# 800U-R3N3_V1_0.net
KiCad netlist of a schematic drawn in Altium Designer
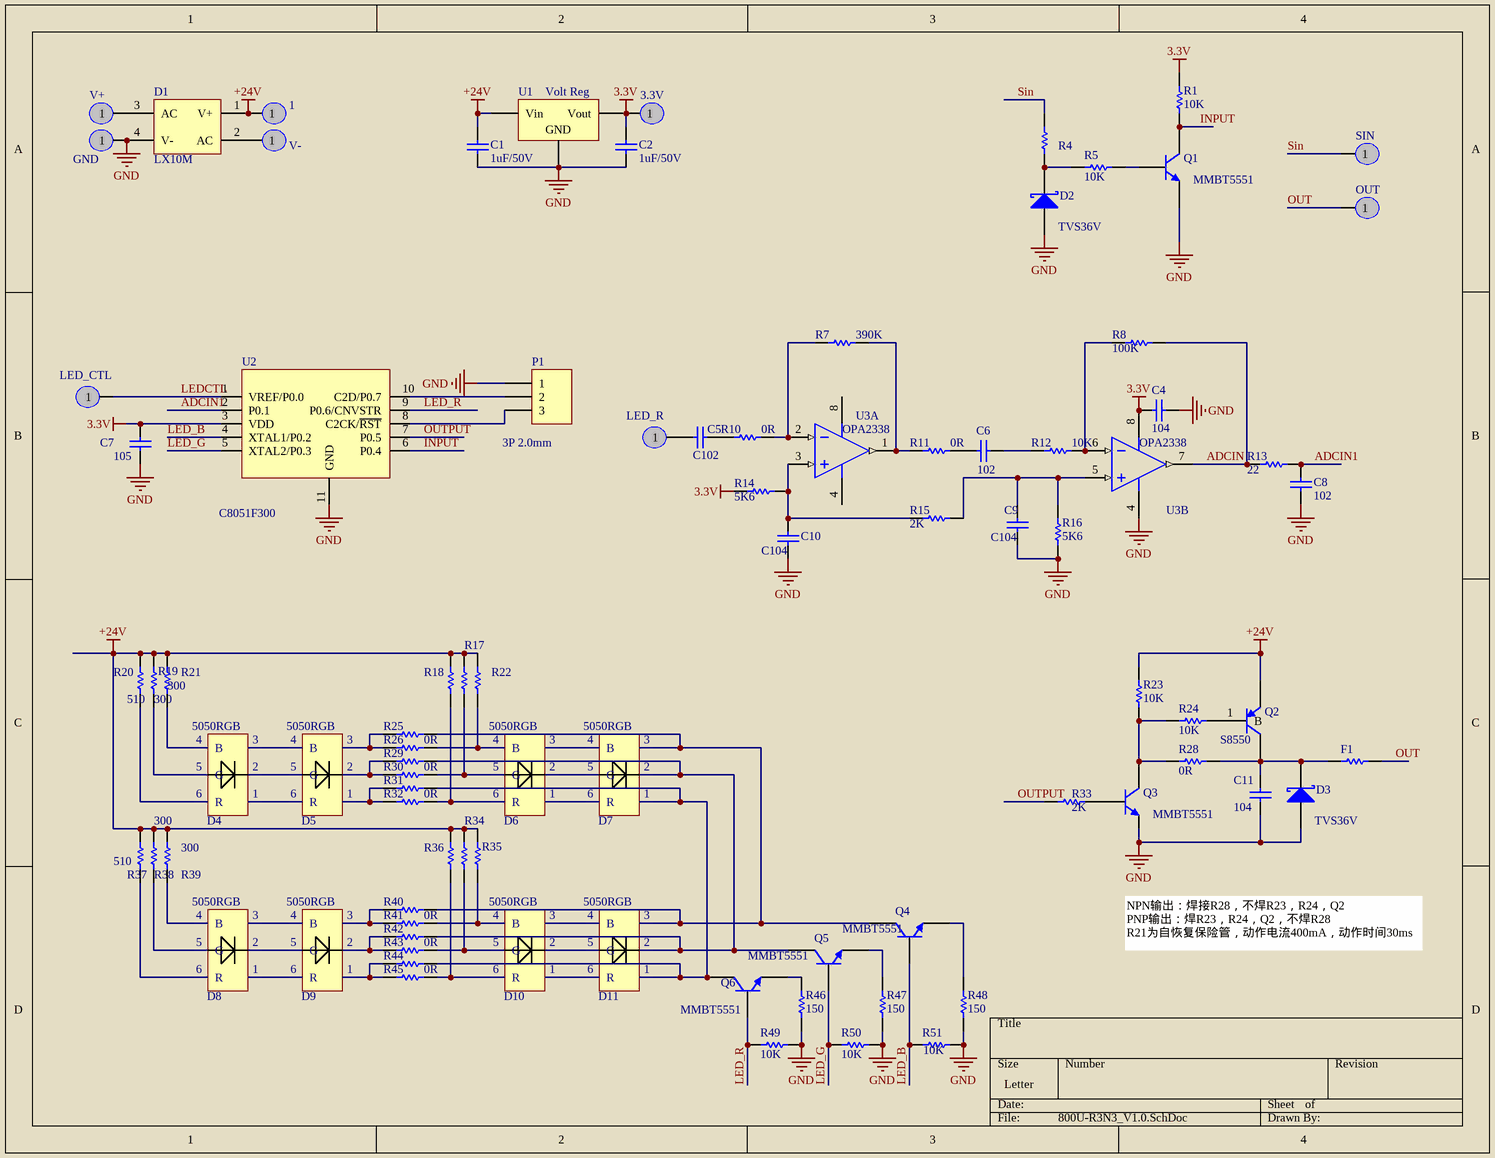
[diagram p0: 800U-R3N3_V1.0.SchDoc]

(export (version "E")
  (design (tool "Eeschema 10.0.6"))
  (components
    (comp (ref "1") (value "~") (footprint "HOLE_SMD") (libsource (lib "MODBUS_V1.0") (part "焊盘")))
    (comp (ref "3.3V") (value "~") (footprint "HOLE_SMD") (libsource (lib "MODBUS_V1.0") (part "焊盘")))
    (comp (ref "C1")
      (value "1uF/50V")
      (footprint "C0603")
      (description "贴片电容")
      (fields (field (name "PUBLISHER") "Altium Limited"))
      (libsource (lib "Miscellaneous Devices") (part "Cap"))
    )
    (comp (ref "C2")
      (value "1uF/50V")
      (footprint "C0603")
      (description "贴片电容")
      (fields (field (name "PUBLISHER") "Altium Limited"))
      (libsource (lib "Miscellaneous Devices") (part "Cap"))
    )
    (comp (ref "C4")
      (value "104")
      (footprint "C0603")
      (description "Capacitor")
      (fields (field (name "Comment") "C106") (field (name "PUBLISHER") "Altium Limited"))
      (libsource (lib "TMJD1.0") (part "Cap"))
    )
    (comp (ref "C5")
      (value "C102")
      (footprint "C0603")
      (description "Capacitor")
      (fields (field (name "Comment") "C104") (field (name "PUBLISHER") "Altium Limited"))
      (libsource (lib "TMJD1.0") (part "Cap"))
    )
    (comp (ref "C6")
      (value "102")
      (footprint "C0603")
      (description "Capacitor")
      (fields (field (name "Comment") "C104") (field (name "PUBLISHER") "Altium Limited"))
      (libsource (lib "TMJD1.0") (part "Cap"))
    )
    (comp (ref "C7")
      (value "105")
      (footprint "C0603")
      (description "贴片电容")
      (fields (field (name "PUBLISHER") "Altium Limited"))
      (libsource (lib "TMJD1.0") (part "Cap"))
    )
    (comp (ref "C8")
      (value "102")
      (footprint "C0603")
      (description "Capacitor")
      (fields (field (name "Comment") "C104") (field (name "PUBLISHER") "Altium Limited"))
      (libsource (lib "TMJD1.0") (part "Cap"))
    )
    (comp (ref "C9")
      (value "C104")
      (footprint "C0603")
      (description "Capacitor")
      (fields (field (name "PUBLISHER") "Altium Limited"))
      (libsource (lib "TMJD1.0") (part "Cap"))
    )
    (comp (ref "C10")
      (value "C104")
      (footprint "C0603")
      (description "Capacitor")
      (fields (field (name "PUBLISHER") "Altium Limited"))
      (libsource (lib "TMJD1.0") (part "Cap"))
    )
    (comp (ref "C11")
      (value "104")
      (footprint "C0603")
      (description "贴片电容")
      (fields (field (name "PUBLISHER") "Altium Limited"))
      (libsource (lib "TMJD1.0") (part "Cap"))
    )
    (comp (ref "D1")
      (value "LX10M")
      (footprint "桥堆 3.8*3.5")
      (description "贴片桥堆")
      (libsource (lib "Miscellaneous Devices") (part "Bridge2"))
    )
    (comp (ref "D2")
      (value "TVS36V")
      (footprint "HSMA")
      (description "贴片TVS")
      (fields (field (name "PUBLISHER") "Altium Limited"))
      (libsource (lib "*") (part "D Schottky"))
    )
    (comp (ref "D3")
      (value "TVS36V")
      (footprint "HSMA")
      (description "贴片TVS")
      (fields (field (name "PUBLISHER") "Altium Limited"))
      (libsource (lib "*") (part "D Schottky"))
    )
    (comp (ref "D4")
      (value "5050RGB")
      (footprint "5050RGB")
      (description "贴片RBG发光管")
      (libsource (lib "MODBUS_V1.0") (part "5050RGB"))
    )
    (comp (ref "D5")
      (value "5050RGB")
      (footprint "5050RGB")
      (description "贴片RBG发光管")
      (libsource (lib "MODBUS_V1.0") (part "5050RGB"))
    )
    (comp (ref "D6")
      (value "5050RGB")
      (footprint "5050RGB")
      (description "贴片RBG发光管")
      (libsource (lib "MODBUS_V1.0") (part "5050RGB"))
    )
    (comp (ref "D7")
      (value "5050RGB")
      (footprint "5050RGB")
      (description "贴片RBG发光管")
      (libsource (lib "MODBUS_V1.0") (part "5050RGB"))
    )
    (comp (ref "D8")
      (value "5050RGB")
      (footprint "5050RGB")
      (description "贴片RBG发光管")
      (libsource (lib "MODBUS_V1.0") (part "5050RGB"))
    )
    (comp (ref "D9")
      (value "5050RGB")
      (footprint "5050RGB")
      (description "贴片RBG发光管")
      (libsource (lib "MODBUS_V1.0") (part "5050RGB"))
    )
    (comp (ref "D10")
      (value "5050RGB")
      (footprint "5050RGB")
      (description "贴片RBG发光管")
      (libsource (lib "MODBUS_V1.0") (part "5050RGB"))
    )
    (comp (ref "D11")
      (value "5050RGB")
      (footprint "5050RGB")
      (description "贴片RBG发光管")
      (libsource (lib "MODBUS_V1.0") (part "5050RGB"))
    )
    (comp (ref "F1")
      (value "SMD1206P016")
      (footprint "1206")
      (description "Semiconductor Resistor")
      (fields (field (name "PUBLISHER") "Altium Limited"))
      (libsource (lib "Miscellaneous Devices") (part "Res Semi"))
    )
    (comp (ref "GND") (value "~") (footprint "HOLE_SMD") (libsource (lib "MODBUS_V1.0") (part "焊盘")))
    (comp (ref "LED_CTL") (value "~") (footprint "HOLE_SMD") (libsource (lib "MODBUS_V1.0") (part "焊盘")))
    (comp (ref "LED_R") (value "~") (footprint "HOLE_SMD") (libsource (lib "MODBUS_V1.0") (part "焊盘")))
    (comp (ref "OUT") (value "~") (footprint "HOLE_SMD") (libsource (lib "MODBUS_V1.0") (part "焊盘")))
    (comp (ref "P1")
      (value "3P 2.0mm")
      (footprint "SIP3")
      (description "插座")
      (fields (field (name "PUBLISHER") "Altium Limited"))
      (libsource (lib "Miscellaneous Connectors") (part "MHDR1X3"))
    )
    (comp (ref "Q1")
      (value "MMBT5551")
      (footprint "SOT-23")
      (description "贴片NPN三极管")
      (libsource (lib "Miscellaneous Devices") (part "NPN"))
    )
    (comp (ref "Q2")
      (value "S8550")
      (footprint "SOT-23")
      (description "贴片PNP三极管")
      (libsource (lib "MODBUS_V1.0") (part "S8550"))
    )
    (comp (ref "Q3")
      (value "MMBT5551")
      (footprint "SOT-23")
      (description "NPN三极管")
      (fields (field (name "Comment") "贴片三极管"))
      (libsource (lib "Miscellaneous Devices") (part "NPN"))
    )
    (comp (ref "Q4")
      (value "MMBT5551")
      (footprint "SOT-23")
      (description "贴片NPN三极管")
      (libsource (lib "Miscellaneous Devices") (part "NPN"))
    )
    (comp (ref "Q5")
      (value "MMBT5551")
      (footprint "SOT-23")
      (description "贴片NPN三极管")
      (libsource (lib "Miscellaneous Devices") (part "NPN"))
    )
    (comp (ref "Q6")
      (value "MMBT5551")
      (footprint "SOT-23")
      (description "贴片NPN三极管")
      (libsource (lib "Miscellaneous Devices") (part "NPN"))
    )
    (comp (ref "R1")
      (value "10K")
      (footprint "R0603")
      (description "贴片电阻")
      (libsource (lib "Miscellaneous Devices") (part "Res Semi"))
    )
    (comp (ref "R4")
      (value "SMD1206P016")
      (footprint "R0603")
      (description "Semiconductor Resistor")
      (fields (field (name "PUBLISHER") "Altium Limited"))
      (libsource (lib "Miscellaneous Devices") (part "Res Semi"))
    )
    (comp (ref "R5")
      (value "10K")
      (footprint "R0603")
      (description "贴片电阻")
      (libsource (lib "Miscellaneous Devices") (part "Res Semi"))
    )
    (comp (ref "R7")
      (value "~")
      (footprint "R0603")
      (description "Semiconductor Resistor")
      (fields (field (name "ALTIUM_UNNAMED_1") "390K"))
      (libsource (lib "Miscellaneous Devices") (part "Res Semi"))
    )
    (comp (ref "R8")
      (value "~")
      (footprint "R0603")
      (description "Semiconductor Resistor")
      (fields (field (name "ALTIUM_UNNAMED_1") "100K"))
      (libsource (lib "Miscellaneous Devices") (part "Res Semi"))
    )
    (comp (ref "R10")
      (value "~")
      (footprint "R0603")
      (description "Semiconductor Resistor")
      (fields (field (name "ALTIUM_UNNAMED_1") "0R"))
      (libsource (lib "Miscellaneous Devices") (part "Res Semi"))
    )
    (comp (ref "R11")
      (value "~")
      (footprint "R0603")
      (description "Semiconductor Resistor")
      (fields (field (name "ALTIUM_UNNAMED_1") "0R"))
      (libsource (lib "Miscellaneous Devices") (part "Res Semi"))
    )
    (comp (ref "R12")
      (value "~")
      (footprint "R0603")
      (description "Semiconductor Resistor")
      (fields (field (name "ALTIUM_UNNAMED_1") "10K"))
      (libsource (lib "Miscellaneous Devices") (part "Res Semi"))
    )
    (comp (ref "R13")
      (value "~")
      (footprint "R0603")
      (description "Semiconductor Resistor")
      (fields (field (name "ALTIUM_UNNAMED_1") "22"))
      (libsource (lib "Miscellaneous Devices") (part "Res Semi"))
    )
    (comp (ref "R14")
      (value "~")
      (footprint "R0603")
      (description "Semiconductor Resistor")
      (fields (field (name "ALTIUM_UNNAMED_1") "5K6"))
      (libsource (lib "Miscellaneous Devices") (part "Res Semi"))
    )
    (comp (ref "R15")
      (value "~")
      (footprint "R0603")
      (description "Semiconductor Resistor")
      (fields (field (name "ALTIUM_UNNAMED_1") "2K"))
      (libsource (lib "Miscellaneous Devices") (part "Res Semi"))
    )
    (comp (ref "R16")
      (value "~")
      (footprint "R0603")
      (description "Semiconductor Resistor")
      (fields (field (name "ALTIUM_UNNAMED_1") "5K6"))
      (libsource (lib "Miscellaneous Devices") (part "Res Semi"))
    )
    (comp (ref "R17")
      (value "~")
      (footprint "2010")
      (description "贴片电阻")
      (libsource (lib "Miscellaneous Devices") (part "Res Semi"))
    )
    (comp (ref "R18")
      (value "~")
      (footprint "2010")
      (description "贴片电阻")
      (libsource (lib "Miscellaneous Devices") (part "Res Semi"))
    )
    (comp (ref "R19")
      (value "300")
      (footprint "2010")
      (description "贴片电阻")
      (libsource (lib "Miscellaneous Devices") (part "Res Semi"))
    )
    (comp (ref "R20")
      (value "510")
      (footprint "2010")
      (description "贴片电阻")
      (libsource (lib "Miscellaneous Devices") (part "Res Semi"))
    )
    (comp (ref "R21")
      (value "300")
      (footprint "2010")
      (description "贴片电阻")
      (libsource (lib "Miscellaneous Devices") (part "Res Semi"))
    )
    (comp (ref "R22")
      (value "~")
      (footprint "2010")
      (description "贴片电阻")
      (libsource (lib "Miscellaneous Devices") (part "Res Semi"))
    )
    (comp (ref "R23")
      (value "10K")
      (footprint "R0603")
      (description "贴片电阻")
      (libsource (lib "Miscellaneous Devices") (part "Res Semi"))
    )
    (comp (ref "R24")
      (value "10K")
      (footprint "R0603")
      (description "贴片电阻")
      (libsource (lib "Miscellaneous Devices") (part "Res Semi"))
    )
    (comp (ref "R25")
      (value "~")
      (footprint "R0603")
      (description "贴片电阻")
      (libsource (lib "Miscellaneous Devices") (part "Res Semi"))
    )
    (comp (ref "R26")
      (value "0R")
      (footprint "R0603")
      (description "贴片电阻")
      (libsource (lib "Miscellaneous Devices") (part "Res Semi"))
    )
    (comp (ref "R28")
      (value "0R")
      (footprint "R0603")
      (description "贴片电阻")
      (libsource (lib "Miscellaneous Devices") (part "Res Semi"))
    )
    (comp (ref "R29")
      (value "~")
      (footprint "R0603")
      (description "贴片电阻")
      (libsource (lib "Miscellaneous Devices") (part "Res Semi"))
    )
    (comp (ref "R30")
      (value "0R")
      (footprint "R0603")
      (description "贴片电阻")
      (libsource (lib "Miscellaneous Devices") (part "Res Semi"))
    )
    (comp (ref "R31")
      (value "~")
      (footprint "R0603")
      (description "贴片电阻")
      (libsource (lib "Miscellaneous Devices") (part "Res Semi"))
    )
    (comp (ref "R32")
      (value "0R")
      (footprint "R0603")
      (description "贴片电阻")
      (libsource (lib "Miscellaneous Devices") (part "Res Semi"))
    )
    (comp (ref "R33")
      (value "2K")
      (footprint "R0603")
      (description "贴片电阻")
      (libsource (lib "Miscellaneous Devices") (part "Res Semi"))
    )
    (comp (ref "R34")
      (value "~")
      (footprint "2010")
      (description "贴片电阻")
      (libsource (lib "Miscellaneous Devices") (part "Res Semi"))
    )
    (comp (ref "R35")
      (value "~")
      (footprint "2010")
      (description "贴片电阻")
      (libsource (lib "Miscellaneous Devices") (part "Res Semi"))
    )
    (comp (ref "R36")
      (value "~")
      (footprint "2010")
      (description "贴片电阻")
      (libsource (lib "Miscellaneous Devices") (part "Res Semi"))
    )
    (comp (ref "R37")
      (value "510")
      (footprint "2010")
      (description "贴片电阻")
      (libsource (lib "Miscellaneous Devices") (part "Res Semi"))
    )
    (comp (ref "R38")
      (value "300")
      (footprint "2010")
      (description "贴片电阻")
      (libsource (lib "Miscellaneous Devices") (part "Res Semi"))
    )
    (comp (ref "R39")
      (value "300")
      (footprint "2010")
      (description "贴片电阻")
      (libsource (lib "Miscellaneous Devices") (part "Res Semi"))
    )
    (comp (ref "R40")
      (value "~")
      (footprint "R0603")
      (description "贴片电阻")
      (libsource (lib "Miscellaneous Devices") (part "Res Semi"))
    )
    (comp (ref "R41")
      (value "0R")
      (footprint "R0603")
      (description "贴片电阻")
      (libsource (lib "Miscellaneous Devices") (part "Res Semi"))
    )
    (comp (ref "R42")
      (value "~")
      (footprint "R0603")
      (description "贴片电阻")
      (libsource (lib "Miscellaneous Devices") (part "Res Semi"))
    )
    (comp (ref "R43")
      (value "0R")
      (footprint "R0603")
      (description "贴片电阻")
      (libsource (lib "Miscellaneous Devices") (part "Res Semi"))
    )
    (comp (ref "R44")
      (value "~")
      (footprint "R0603")
      (description "贴片电阻")
      (libsource (lib "Miscellaneous Devices") (part "Res Semi"))
    )
    (comp (ref "R45")
      (value "0R")
      (footprint "R0603")
      (description "贴片电阻")
      (libsource (lib "Miscellaneous Devices") (part "Res Semi"))
    )
    (comp (ref "R46")
      (value "150")
      (footprint "2010")
      (description "贴片电阻")
      (libsource (lib "Miscellaneous Devices") (part "Res Semi"))
    )
    (comp (ref "R47")
      (value "150")
      (footprint "2010")
      (description "贴片电阻")
      (libsource (lib "Miscellaneous Devices") (part "Res Semi"))
    )
    (comp (ref "R48")
      (value "150")
      (footprint "2010")
      (description "贴片电阻")
      (libsource (lib "Miscellaneous Devices") (part "Res Semi"))
    )
    (comp (ref "R49")
      (value "10K")
      (footprint "R0603")
      (description "贴片电阻")
      (libsource (lib "Miscellaneous Devices") (part "Res Semi"))
    )
    (comp (ref "R50")
      (value "10K")
      (footprint "R0603")
      (description "贴片电阻")
      (libsource (lib "Miscellaneous Devices") (part "Res Semi"))
    )
    (comp (ref "R51")
      (value "10K")
      (footprint "R0603")
      (description "贴片电阻")
      (libsource (lib "Miscellaneous Devices") (part "Res Semi"))
    )
    (comp (ref "SIN") (value "~") (footprint "HOLE_SMD") (libsource (lib "MODBUS_V1.0") (part "焊盘")))
    (comp (ref "U1")
      (value "Volt Reg")
      (footprint "SOT-23")
      (description "Voltage Regulator")
      (fields (field (name "PUBLISHER") "Altium Limited"))
      (libsource (lib "Miscellaneous Devices") (part "Volt Reg"))
    )
    (comp (ref "U2")
      (value "C8051F300")
      (footprint "QFN-11")
      (description "贴片芯片")
      (libsource (lib "集成块") (part "PIC16C505"))
    )
    (comp (ref "U3")
      (value "OPA2338")
      (footprint "SO-8")
      (description "Dual Low Noise, Audio Amplifier")
      (fields (field (name "PUBLISHER") "Altium Limited"))
      (libsource (lib "Motorola Amplifier Audio Amplifier") (part "LM833D"))
    )
    (comp (ref "V+") (value "~") (footprint "HOLE_SMD") (libsource (lib "MODBUS_V1.0") (part "焊盘")))
    (comp (ref "V-") (value "~") (footprint "HOLE_SMD") (libsource (lib "MODBUS_V1.0") (part "焊盘")))
  )
  (nets
    (net (code "1") (name "+24V") (class "Default")
      (node (ref "1") (pin "1") (pinfunction "1_1") (pintype "passive"))
      (node (ref "C1") (pin "1") (pinfunction "1_1") (pintype "passive"))
      (node (ref "D1") (pin "1") (pinfunction "V+_1") (pintype "passive"))
      (node (ref "Q2") (pin "2") (pinfunction "E_2") (pintype "passive"))
      (node (ref "R17") (pin "1") (pinfunction "1_1") (pintype "passive"))
      (node (ref "R18") (pin "1") (pinfunction "1_1") (pintype "passive"))
      (node (ref "R19") (pin "1") (pinfunction "1_1") (pintype "passive"))
      (node (ref "R20") (pin "1") (pinfunction "1_1") (pintype "passive"))
      (node (ref "R21") (pin "1") (pinfunction "1_1") (pintype "passive"))
      (node (ref "R22") (pin "1") (pinfunction "1_1") (pintype "passive"))
      (node (ref "R23") (pin "2") (pinfunction "2_2") (pintype "passive"))
      (node (ref "R34") (pin "1") (pinfunction "1_1") (pintype "passive"))
      (node (ref "R35") (pin "1") (pinfunction "1_1") (pintype "passive"))
      (node (ref "R36") (pin "1") (pinfunction "1_1") (pintype "passive"))
      (node (ref "R37") (pin "1") (pinfunction "1_1") (pintype "passive"))
      (node (ref "R38") (pin "1") (pinfunction "1_1") (pintype "passive"))
      (node (ref "R39") (pin "1") (pinfunction "1_1") (pintype "passive"))
      (node (ref "U1") (pin "3") (pinfunction "Vin_3") (pintype "passive"))
    )
    (net (code "2") (name "/ADCIN") (class "Default")
      (node (ref "R13") (pin "1") (pinfunction "1_1") (pintype "passive"))
      (node (ref "R8") (pin "2") (pinfunction "2_2") (pintype "passive"))
      (node (ref "U3") (pin "7") (pinfunction "OUT_7") (pintype "output"))
    )
    (net (code "3") (name "/ADCIN1") (class "Default")
      (node (ref "C8") (pin "2") (pinfunction "2_2") (pintype "passive"))
      (node (ref "R13") (pin "2") (pinfunction "2_2") (pintype "passive"))
      (node (ref "U2") (pin "2") (pinfunction "P0.1_2") (pintype "passive"))
    )
    (net (code "4") (name "/INPUT") (class "Default")
      (node (ref "Q1") (pin "3") (pinfunction "C_3") (pintype "passive"))
      (node (ref "R1") (pin "1") (pinfunction "1_1") (pintype "passive"))
      (node (ref "U2") (pin "6") (pinfunction "P0.4_6") (pintype "passive"))
    )
    (net (code "5") (name "/LEDCTL") (class "Default")
      (node (ref "LED_CTL") (pin "1") (pinfunction "1_1") (pintype "passive"))
      (node (ref "U2") (pin "1") (pinfunction "VREF/P0.0_1") (pintype "passive"))
    )
    (net (code "6") (name "/LED_B") (class "Default")
      (node (ref "Q4") (pin "1") (pinfunction "B_1") (pintype "passive"))
      (node (ref "R51") (pin "1") (pinfunction "1_1") (pintype "passive"))
      (node (ref "U2") (pin "4") (pinfunction "XTAL1/P0.2_4") (pintype "passive"))
    )
    (net (code "7") (name "/LED_G") (class "Default")
      (node (ref "Q5") (pin "1") (pinfunction "B_1") (pintype "passive"))
      (node (ref "R50") (pin "1") (pinfunction "1_1") (pintype "passive"))
      (node (ref "U2") (pin "5") (pinfunction "XTAL2/P0.3_5") (pintype "passive"))
    )
    (net (code "8") (name "/LED_R") (class "Default")
      (node (ref "Q6") (pin "1") (pinfunction "B_1") (pintype "passive"))
      (node (ref "R49") (pin "1") (pinfunction "1_1") (pintype "passive"))
      (node (ref "U2") (pin "9") (pinfunction "P0.6/CNVSTR_9") (pintype "passive"))
    )
    (net (code "9") (name "/OUT") (class "Default")
      (node (ref "F1") (pin "2") (pinfunction "2_2") (pintype "passive"))
      (node (ref "OUT") (pin "1") (pinfunction "1_1") (pintype "passive"))
    )
    (net (code "10") (name "/OUTPUT") (class "Default")
      (node (ref "R33") (pin "2") (pinfunction "2_2") (pintype "passive"))
      (node (ref "U2") (pin "7") (pinfunction "P0.5_7") (pintype "passive"))
    )
    (net (code "11") (name "/Sin") (class "Default")
      (node (ref "R4") (pin "2") (pinfunction "2_2") (pintype "passive"))
      (node (ref "SIN") (pin "1") (pinfunction "1_1") (pintype "passive"))
    )
    (net (code "12") (name "3.3V") (class "Default")
      (node (ref "3.3V") (pin "1") (pinfunction "1_1") (pintype "passive"))
      (node (ref "C2") (pin "1") (pinfunction "1_1") (pintype "passive"))
      (node (ref "C4") (pin "1") (pinfunction "1_1") (pintype "passive"))
      (node (ref "C7") (pin "1") (pinfunction "1_1") (pintype "passive"))
      (node (ref "R1") (pin "2") (pinfunction "2_2") (pintype "passive"))
      (node (ref "R14") (pin "1") (pinfunction "1_1") (pintype "passive"))
      (node (ref "U1") (pin "2") (pinfunction "Vout_2") (pintype "passive"))
      (node (ref "U2") (pin "3") (pinfunction "VDD_3") (pintype "passive"))
      (node (ref "U3") (pin "8") (pinfunction "VCC_8") (pintype "power_in"))
    )
    (net (code "13") (name "GND") (class "Default")
      (node (ref "C1") (pin "2") (pinfunction "2_2") (pintype "passive"))
      (node (ref "C10") (pin "2") (pinfunction "2_2") (pintype "passive"))
      (node (ref "C11") (pin "2") (pinfunction "2_2") (pintype "passive"))
      (node (ref "C2") (pin "2") (pinfunction "2_2") (pintype "passive"))
      (node (ref "C4") (pin "2") (pinfunction "2_2") (pintype "passive"))
      (node (ref "C7") (pin "2") (pinfunction "2_2") (pintype "passive"))
      (node (ref "C8") (pin "1") (pinfunction "1_1") (pintype "passive"))
      (node (ref "C9") (pin "2") (pinfunction "2_2") (pintype "passive"))
      (node (ref "D1") (pin "4") (pinfunction "V-_4") (pintype "passive"))
      (node (ref "D2") (pin "1") (pinfunction "A_1") (pintype "passive"))
      (node (ref "D3") (pin "1") (pinfunction "A_1") (pintype "passive"))
      (node (ref "GND") (pin "1") (pinfunction "1_1") (pintype "passive"))
      (node (ref "P1") (pin "1") (pinfunction "1_1") (pintype "passive"))
      (node (ref "Q1") (pin "2") (pinfunction "E_2") (pintype "passive"))
      (node (ref "Q3") (pin "2") (pinfunction "E_2") (pintype "passive"))
      (node (ref "R16") (pin "1") (pinfunction "1_1") (pintype "passive"))
      (node (ref "R46") (pin "2") (pinfunction "2_2") (pintype "passive"))
      (node (ref "R47") (pin "2") (pinfunction "2_2") (pintype "passive"))
      (node (ref "R48") (pin "2") (pinfunction "2_2") (pintype "passive"))
      (node (ref "R49") (pin "2") (pinfunction "2_2") (pintype "passive"))
      (node (ref "R50") (pin "2") (pinfunction "2_2") (pintype "passive"))
      (node (ref "R51") (pin "2") (pinfunction "2_2") (pintype "passive"))
      (node (ref "U1") (pin "1") (pinfunction "GND_1") (pintype "passive"))
      (node (ref "U2") (pin "11") (pinfunction "GND_11") (pintype "passive"))
      (node (ref "U3") (pin "4") (pinfunction "VEE_4") (pintype "power_in"))
    )
    (net (code "14") (name "Net-(C5-Pad1)") (class "Default")
      (node (ref "C5") (pin "1") (pinfunction "1_1") (pintype "passive"))
      (node (ref "LED_R") (pin "1") (pinfunction "1_1") (pintype "passive"))
    )
    (net (code "15") (name "Net-(C5-Pad2)") (class "Default")
      (node (ref "C5") (pin "2") (pinfunction "2_2") (pintype "passive"))
      (node (ref "R10") (pin "1") (pinfunction "1_1") (pintype "passive"))
    )
    (net (code "16") (name "Net-(C6-Pad1)") (class "Default")
      (node (ref "C6") (pin "1") (pinfunction "1_1") (pintype "passive"))
      (node (ref "R11") (pin "2") (pinfunction "2_2") (pintype "passive"))
    )
    (net (code "17") (name "Net-(C6-Pad2)") (class "Default")
      (node (ref "C6") (pin "2") (pinfunction "2_2") (pintype "passive"))
      (node (ref "R12") (pin "1") (pinfunction "1_1") (pintype "passive"))
    )
    (net (code "18") (name "Net-(D1-AC-Pad2)") (class "Default")
      (node (ref "D1") (pin "2") (pinfunction "AC_2") (pintype "passive"))
      (node (ref "V-") (pin "1") (pinfunction "1_1") (pintype "passive"))
    )
    (net (code "19") (name "Net-(D1-AC-Pad3)") (class "Default")
      (node (ref "D1") (pin "3") (pinfunction "AC_3") (pintype "passive"))
      (node (ref "V+") (pin "1") (pinfunction "1_1") (pintype "passive"))
    )
    (net (code "20") (name "Net-(D2-K)") (class "Default")
      (node (ref "D2") (pin "2") (pinfunction "K_2") (pintype "passive"))
      (node (ref "R4") (pin "1") (pinfunction "1_1") (pintype "passive"))
      (node (ref "R5") (pin "1") (pinfunction "1_1") (pintype "passive"))
    )
    (net (code "21") (name "Net-(D3-K)") (class "Default")
      (node (ref "C11") (pin "1") (pinfunction "1_1") (pintype "passive"))
      (node (ref "D3") (pin "2") (pinfunction "K_2") (pintype "passive"))
      (node (ref "F1") (pin "1") (pinfunction "1_1") (pintype "passive"))
      (node (ref "Q2") (pin "3") (pinfunction "C_3") (pintype "passive"))
      (node (ref "R28") (pin "2") (pinfunction "2_2") (pintype "passive"))
    )
    (net (code "22") (name "Net-(D4-B)") (class "Default")
      (node (ref "D4") (pin "4") (pinfunction "B_4") (pintype "passive"))
      (node (ref "R21") (pin "2") (pinfunction "2_2") (pintype "passive"))
    )
    (net (code "23") (name "Net-(D4-G)") (class "Default")
      (node (ref "D4") (pin "5") (pinfunction "G_5") (pintype "passive"))
      (node (ref "R19") (pin "2") (pinfunction "2_2") (pintype "passive"))
    )
    (net (code "24") (name "Net-(D4-R)") (class "Default")
      (node (ref "D4") (pin "6") (pinfunction "R_6") (pintype "passive"))
      (node (ref "R20") (pin "2") (pinfunction "2_2") (pintype "passive"))
    )
    (net (code "25") (name "Net-(D5-B)") (class "Default")
      (node (ref "D4") (pin "3") (pintype "passive"))
      (node (ref "D5") (pin "4") (pinfunction "B_4") (pintype "passive"))
    )
    (net (code "26") (name "Net-(D5-G)") (class "Default")
      (node (ref "D4") (pin "2") (pintype "passive"))
      (node (ref "D5") (pin "5") (pinfunction "G_5") (pintype "passive"))
    )
    (net (code "27") (name "Net-(D5-Pad1)") (class "Default")
      (node (ref "D5") (pin "1") (pintype "passive"))
      (node (ref "R31") (pin "1") (pinfunction "1_1") (pintype "passive"))
      (node (ref "R32") (pin "1") (pinfunction "1_1") (pintype "passive"))
    )
    (net (code "28") (name "Net-(D5-Pad2)") (class "Default")
      (node (ref "D5") (pin "2") (pintype "passive"))
      (node (ref "R29") (pin "1") (pinfunction "1_1") (pintype "passive"))
      (node (ref "R30") (pin "1") (pinfunction "1_1") (pintype "passive"))
    )
    (net (code "29") (name "Net-(D5-Pad3)") (class "Default")
      (node (ref "D5") (pin "3") (pintype "passive"))
      (node (ref "R25") (pin "1") (pinfunction "1_1") (pintype "passive"))
      (node (ref "R26") (pin "1") (pinfunction "1_1") (pintype "passive"))
    )
    (net (code "30") (name "Net-(D5-R)") (class "Default")
      (node (ref "D4") (pin "1") (pintype "passive"))
      (node (ref "D5") (pin "6") (pinfunction "R_6") (pintype "passive"))
    )
    (net (code "31") (name "Net-(D6-B)") (class "Default")
      (node (ref "D6") (pin "4") (pinfunction "B_4") (pintype "passive"))
      (node (ref "R22") (pin "2") (pinfunction "2_2") (pintype "passive"))
      (node (ref "R26") (pin "2") (pinfunction "2_2") (pintype "passive"))
    )
    (net (code "32") (name "Net-(D6-G)") (class "Default")
      (node (ref "D6") (pin "5") (pinfunction "G_5") (pintype "passive"))
      (node (ref "R17") (pin "2") (pinfunction "2_2") (pintype "passive"))
      (node (ref "R30") (pin "2") (pinfunction "2_2") (pintype "passive"))
    )
    (net (code "33") (name "Net-(D6-R)") (class "Default")
      (node (ref "D6") (pin "6") (pinfunction "R_6") (pintype "passive"))
      (node (ref "R18") (pin "2") (pinfunction "2_2") (pintype "passive"))
      (node (ref "R32") (pin "2") (pinfunction "2_2") (pintype "passive"))
    )
    (net (code "34") (name "Net-(D7-B)") (class "Default")
      (node (ref "D6") (pin "3") (pintype "passive"))
      (node (ref "D7") (pin "4") (pinfunction "B_4") (pintype "passive"))
    )
    (net (code "35") (name "Net-(D7-G)") (class "Default")
      (node (ref "D6") (pin "2") (pintype "passive"))
      (node (ref "D7") (pin "5") (pinfunction "G_5") (pintype "passive"))
    )
    (net (code "36") (name "Net-(D7-R)") (class "Default")
      (node (ref "D6") (pin "1") (pintype "passive"))
      (node (ref "D7") (pin "6") (pinfunction "R_6") (pintype "passive"))
    )
    (net (code "37") (name "Net-(D8-B)") (class "Default")
      (node (ref "D8") (pin "4") (pinfunction "B_4") (pintype "passive"))
      (node (ref "R39") (pin "2") (pinfunction "2_2") (pintype "passive"))
    )
    (net (code "38") (name "Net-(D8-G)") (class "Default")
      (node (ref "D8") (pin "5") (pinfunction "G_5") (pintype "passive"))
      (node (ref "R38") (pin "2") (pinfunction "2_2") (pintype "passive"))
    )
    (net (code "39") (name "Net-(D8-R)") (class "Default")
      (node (ref "D8") (pin "6") (pinfunction "R_6") (pintype "passive"))
      (node (ref "R37") (pin "2") (pinfunction "2_2") (pintype "passive"))
    )
    (net (code "40") (name "Net-(D9-B)") (class "Default")
      (node (ref "D8") (pin "3") (pintype "passive"))
      (node (ref "D9") (pin "4") (pinfunction "B_4") (pintype "passive"))
    )
    (net (code "41") (name "Net-(D9-G)") (class "Default")
      (node (ref "D8") (pin "2") (pintype "passive"))
      (node (ref "D9") (pin "5") (pinfunction "G_5") (pintype "passive"))
    )
    (net (code "42") (name "Net-(D9-Pad1)") (class "Default")
      (node (ref "D9") (pin "1") (pintype "passive"))
      (node (ref "R44") (pin "1") (pinfunction "1_1") (pintype "passive"))
      (node (ref "R45") (pin "1") (pinfunction "1_1") (pintype "passive"))
    )
    (net (code "43") (name "Net-(D9-Pad2)") (class "Default")
      (node (ref "D9") (pin "2") (pintype "passive"))
      (node (ref "R42") (pin "1") (pinfunction "1_1") (pintype "passive"))
      (node (ref "R43") (pin "1") (pinfunction "1_1") (pintype "passive"))
    )
    (net (code "44") (name "Net-(D9-Pad3)") (class "Default")
      (node (ref "D9") (pin "3") (pintype "passive"))
      (node (ref "R40") (pin "1") (pinfunction "1_1") (pintype "passive"))
      (node (ref "R41") (pin "1") (pinfunction "1_1") (pintype "passive"))
    )
    (net (code "45") (name "Net-(D9-R)") (class "Default")
      (node (ref "D8") (pin "1") (pintype "passive"))
      (node (ref "D9") (pin "6") (pinfunction "R_6") (pintype "passive"))
    )
    (net (code "46") (name "Net-(D10-B)") (class "Default")
      (node (ref "D10") (pin "4") (pinfunction "B_4") (pintype "passive"))
      (node (ref "R35") (pin "2") (pinfunction "2_2") (pintype "passive"))
      (node (ref "R41") (pin "2") (pinfunction "2_2") (pintype "passive"))
    )
    (net (code "47") (name "Net-(D10-G)") (class "Default")
      (node (ref "D10") (pin "5") (pinfunction "G_5") (pintype "passive"))
      (node (ref "R34") (pin "2") (pinfunction "2_2") (pintype "passive"))
      (node (ref "R43") (pin "2") (pinfunction "2_2") (pintype "passive"))
    )
    (net (code "48") (name "Net-(D10-R)") (class "Default")
      (node (ref "D10") (pin "6") (pinfunction "R_6") (pintype "passive"))
      (node (ref "R36") (pin "2") (pinfunction "2_2") (pintype "passive"))
      (node (ref "R45") (pin "2") (pinfunction "2_2") (pintype "passive"))
    )
    (net (code "49") (name "Net-(D11-B)") (class "Default")
      (node (ref "D10") (pin "3") (pintype "passive"))
      (node (ref "D11") (pin "4") (pinfunction "B_4") (pintype "passive"))
    )
    (net (code "50") (name "Net-(D11-G)") (class "Default")
      (node (ref "D10") (pin "2") (pintype "passive"))
      (node (ref "D11") (pin "5") (pinfunction "G_5") (pintype "passive"))
    )
    (net (code "51") (name "Net-(D11-R)") (class "Default")
      (node (ref "D10") (pin "1") (pintype "passive"))
      (node (ref "D11") (pin "6") (pinfunction "R_6") (pintype "passive"))
    )
    (net (code "52") (name "Net-(Q1-B)") (class "Default")
      (node (ref "Q1") (pin "1") (pinfunction "B_1") (pintype "passive"))
      (node (ref "R5") (pin "2") (pinfunction "2_2") (pintype "passive"))
    )
    (net (code "53") (name "Net-(Q2-B)") (class "Default")
      (node (ref "Q2") (pin "1") (pinfunction "B_1") (pintype "passive"))
      (node (ref "R24") (pin "2") (pinfunction "2_2") (pintype "passive"))
    )
    (net (code "54") (name "Net-(Q3-B)") (class "Default")
      (node (ref "Q3") (pin "1") (pinfunction "B_1") (pintype "passive"))
      (node (ref "R33") (pin "1") (pinfunction "1_1") (pintype "passive"))
    )
    (net (code "55") (name "Net-(Q3-C)") (class "Default")
      (node (ref "Q3") (pin "3") (pinfunction "C_3") (pintype "passive"))
      (node (ref "R23") (pin "1") (pinfunction "1_1") (pintype "passive"))
      (node (ref "R24") (pin "1") (pinfunction "1_1") (pintype "passive"))
      (node (ref "R28") (pin "1") (pinfunction "1_1") (pintype "passive"))
    )
    (net (code "56") (name "Net-(Q4-C)") (class "Default")
      (node (ref "D11") (pin "3") (pintype "passive"))
      (node (ref "D7") (pin "3") (pintype "passive"))
      (node (ref "Q4") (pin "3") (pinfunction "C_3") (pintype "passive"))
      (node (ref "R25") (pin "2") (pinfunction "2_2") (pintype "passive"))
      (node (ref "R40") (pin "2") (pinfunction "2_2") (pintype "passive"))
    )
    (net (code "57") (name "Net-(Q4-E)") (class "Default")
      (node (ref "Q4") (pin "2") (pinfunction "E_2") (pintype "passive"))
      (node (ref "R48") (pin "1") (pinfunction "1_1") (pintype "passive"))
    )
    (net (code "58") (name "Net-(Q5-C)") (class "Default")
      (node (ref "D11") (pin "2") (pintype "passive"))
      (node (ref "D7") (pin "2") (pintype "passive"))
      (node (ref "Q5") (pin "3") (pinfunction "C_3") (pintype "passive"))
      (node (ref "R29") (pin "2") (pinfunction "2_2") (pintype "passive"))
      (node (ref "R42") (pin "2") (pinfunction "2_2") (pintype "passive"))
    )
    (net (code "59") (name "Net-(Q5-E)") (class "Default")
      (node (ref "Q5") (pin "2") (pinfunction "E_2") (pintype "passive"))
      (node (ref "R47") (pin "1") (pinfunction "1_1") (pintype "passive"))
    )
    (net (code "60") (name "Net-(Q6-C)") (class "Default")
      (node (ref "D11") (pin "1") (pintype "passive"))
      (node (ref "D7") (pin "1") (pintype "passive"))
      (node (ref "Q6") (pin "3") (pinfunction "C_3") (pintype "passive"))
      (node (ref "R31") (pin "2") (pinfunction "2_2") (pintype "passive"))
      (node (ref "R44") (pin "2") (pinfunction "2_2") (pintype "passive"))
    )
    (net (code "61") (name "Net-(Q6-E)") (class "Default")
      (node (ref "Q6") (pin "2") (pinfunction "E_2") (pintype "passive"))
      (node (ref "R46") (pin "1") (pinfunction "1_1") (pintype "passive"))
    )
    (net (code "62") (name "Net-(U2-C2CK{slash}~{RST})") (class "Default")
      (node (ref "P1") (pin "3") (pinfunction "3_3") (pintype "passive"))
      (node (ref "U2") (pin "8") (pinfunction "C2CK/~{RST}_8") (pintype "passive"))
    )
    (net (code "63") (name "Net-(U2-C2D{slash}P0.7)") (class "Default")
      (node (ref "P1") (pin "2") (pinfunction "2_2") (pintype "passive"))
      (node (ref "U2") (pin "10") (pinfunction "C2D/P0.7_10") (pintype "passive"))
    )
    (net (code "64") (name "Net-(U3A-IN+)") (class "Default")
      (node (ref "C10") (pin "1") (pinfunction "1_1") (pintype "passive"))
      (node (ref "R14") (pin "2") (pinfunction "2_2") (pintype "passive"))
      (node (ref "R15") (pin "1") (pinfunction "1_1") (pintype "passive"))
      (node (ref "U3") (pin "3") (pinfunction "IN+_3") (pintype "input"))
    )
    (net (code "65") (name "Net-(U3A-IN-)") (class "Default")
      (node (ref "R10") (pin "2") (pinfunction "2_2") (pintype "passive"))
      (node (ref "R7") (pin "1") (pinfunction "1_1") (pintype "passive"))
      (node (ref "U3") (pin "2") (pinfunction "IN-_2") (pintype "input"))
    )
    (net (code "66") (name "Net-(U3A-OUT)") (class "Default")
      (node (ref "R11") (pin "1") (pinfunction "1_1") (pintype "passive"))
      (node (ref "R7") (pin "2") (pinfunction "2_2") (pintype "passive"))
      (node (ref "U3") (pin "1") (pinfunction "OUT_1") (pintype "output"))
    )
    (net (code "67") (name "Net-(U3B-IN+)") (class "Default")
      (node (ref "C9") (pin "1") (pinfunction "1_1") (pintype "passive"))
      (node (ref "R15") (pin "2") (pinfunction "2_2") (pintype "passive"))
      (node (ref "R16") (pin "2") (pinfunction "2_2") (pintype "passive"))
      (node (ref "U3") (pin "5") (pinfunction "IN+_5") (pintype "input"))
    )
    (net (code "68") (name "Net-(U3B-IN-)") (class "Default")
      (node (ref "R12") (pin "2") (pinfunction "2_2") (pintype "passive"))
      (node (ref "R8") (pin "1") (pinfunction "1_1") (pintype "passive"))
      (node (ref "U3") (pin "6") (pinfunction "IN-_6") (pintype "input"))
    )
    (net (code "69") (name "unconnected-(U3A-VCC-Pad8)") (class "Default")
      (node (ref "U3") (pin "8") (pinfunction "VCC_8") (pintype "power_in"))
    )
    (net (code "70") (name "unconnected-(U3A-VEE-Pad4)") (class "Default")
      (node (ref "U3") (pin "4") (pinfunction "VEE_4") (pintype "power_in"))
    )
  )
)
